# 05_Data.net
KiCad netlist of a schematic drawn in Altium Designer
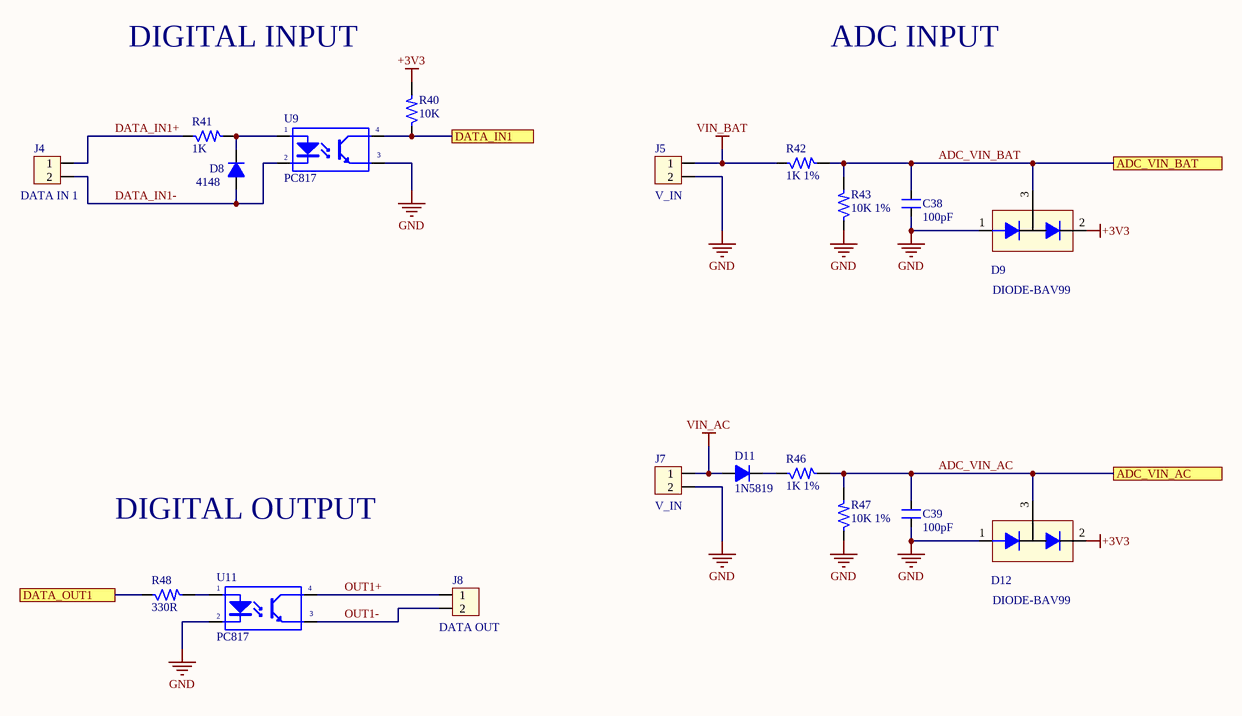
[diagram p0: [05] Data.SchDoc]

(export (version "E")
  (design (tool "Eeschema 10.0.6"))
  (components
    (comp (ref "C38")
      (value "100pF")
      (footprint "C0603 SMT")
      (description "Cap SMD")
      (libsource (lib "khapham") (part "CM"))
    )
    (comp (ref "C39")
      (value "100pF")
      (footprint "C0603 SMT")
      (description "Cap SMD")
      (libsource (lib "khapham") (part "CM"))
    )
    (comp (ref "D8")
      (value "4148")
      (footprint "DO-4148 SMD")
      (description "Diode 1A")
      (libsource (lib "khapham") (part "D1A"))
    )
    (comp (ref "D9")
      (value "DIODE-BAV99")
      (footprint "SOT23")
      (description "ZENER, SOT23,")
      (fields
        (field (name "MANUFACTURER") "ON Semiconductor / Fairchild")
        (field (name "MANUFACTURER PART NUMBER") "BAV99")
        (field (name ".CREATOR") "LeKhaLinh")
        (field (name ".CHECKPCB") "LeKhaLinh")
        (field (name ".CHECKSCH") "LeKhaLinh")
      )
      (libsource (lib "khapham") (part "DIODE-BAV99"))
    )
    (comp (ref "D11")
      (value "1N5819")
      (footprint "SOD123")
      (description "Diode 1A")
      (libsource (lib "khapham") (part "D1A"))
    )
    (comp (ref "D12")
      (value "DIODE-BAV99")
      (footprint "SOT23")
      (description "ZENER, SOT23,")
      (fields
        (field (name "MANUFACTURER") "ON Semiconductor / Fairchild")
        (field (name "MANUFACTURER PART NUMBER") "BAV99")
        (field (name ".CREATOR") "LeKhaLinh")
        (field (name ".CHECKPCB") "LeKhaLinh")
        (field (name ".CHECKSCH") "LeKhaLinh")
      )
      (libsource (lib "khapham") (part "DIODE-BAV99"))
    )
    (comp (ref "J4")
      (value "DATA IN 1")
      (footprint "CON_2.54mm_2")
      (description "Connector 2")
      (libsource (lib "khapham") (part "Con2"))
    )
    (comp (ref "J5")
      (value "V_IN")
      (footprint "CON_2.54mm_2")
      (description "Connector 2")
      (libsource (lib "khapham") (part "Con2"))
    )
    (comp (ref "J7")
      (value "V_IN")
      (footprint "CON_2.54mm_2")
      (description "Connector 2")
      (libsource (lib "khapham") (part "Con2"))
    )
    (comp (ref "J8")
      (value "DATA OUT")
      (footprint "CON_2.54mm_2")
      (description "Connector 2")
      (libsource (lib "") (part "Con2_1"))
    )
    (comp (ref "R40")
      (value "10K")
      (footprint "R0603 -SMT")
      (description "Resistor SMD")
      (libsource (lib "khapham") (part "RM"))
    )
    (comp (ref "R41")
      (value "1K")
      (footprint "R0603 -SMT")
      (description "Resistor SMD")
      (libsource (lib "khapham") (part "RM"))
    )
    (comp (ref "R42")
      (value "1K 1%")
      (footprint "R0603 -SMT")
      (description "Resistor SMD")
      (libsource (lib "khapham") (part "RM"))
    )
    (comp (ref "R43")
      (value "10K 1%")
      (footprint "R0603 -SMT")
      (description "Resistor SMD")
      (libsource (lib "khapham") (part "RM"))
    )
    (comp (ref "R46")
      (value "1K 1%")
      (footprint "R0603 -SMT")
      (description "Resistor SMD")
      (libsource (lib "khapham") (part "RM"))
    )
    (comp (ref "R47")
      (value "10K 1%")
      (footprint "R0603 -SMT")
      (description "Resistor SMD")
      (libsource (lib "khapham") (part "RM"))
    )
    (comp (ref "R48")
      (value "330R")
      (footprint "R0603 -SMT")
      (description "Resistor SMD")
      (libsource (lib "khapham") (part "RM"))
    )
    (comp (ref "U9")
      (value "PC817")
      (footprint "SOP-4-B")
      (description "Single Opto")
      (libsource (lib "khapham") (part "PC817"))
    )
    (comp (ref "U11")
      (value "PC817")
      (footprint "SOP-4-B")
      (description "Single Opto")
      (libsource (lib "khapham") (part "PC817"))
    )
  )
  (nets
    (net (code "1") (name "+3V3") (class "Default")
      (node (ref "D12") (pin "2") (pinfunction "2_2") (pintype "passive"))
      (node (ref "D9") (pin "2") (pinfunction "2_2") (pintype "passive"))
      (node (ref "R40") (pin "2") (pinfunction "2_2") (pintype "passive"))
    )
    (net (code "2") (name "/ADC_VIN_AC") (class "Default")
      (node (ref "C39") (pin "2") (pinfunction "2_2") (pintype "passive"))
      (node (ref "D12") (pin "3") (pinfunction "3_3") (pintype "passive"))
      (node (ref "R46") (pin "2") (pinfunction "2_2") (pintype "passive"))
      (node (ref "R47") (pin "2") (pinfunction "2_2") (pintype "passive"))
    )
    (net (code "3") (name "/ADC_VIN_BAT") (class "Default")
      (node (ref "C38") (pin "2") (pinfunction "2_2") (pintype "passive"))
      (node (ref "D9") (pin "3") (pinfunction "3_3") (pintype "passive"))
      (node (ref "R42") (pin "2") (pinfunction "2_2") (pintype "passive"))
      (node (ref "R43") (pin "2") (pinfunction "2_2") (pintype "passive"))
    )
    (net (code "4") (name "/DATA_IN1") (class "Default")
      (node (ref "R40") (pin "1") (pinfunction "1_1") (pintype "passive"))
      (node (ref "U9") (pin "4") (pinfunction "C_4") (pintype "passive"))
    )
    (net (code "5") (name "/DATA_IN1+") (class "Default")
      (node (ref "J4") (pin "1") (pinfunction "1_1") (pintype "passive"))
      (node (ref "R41") (pin "1") (pinfunction "1_1") (pintype "passive"))
    )
    (net (code "6") (name "/DATA_IN1-") (class "Default")
      (node (ref "D8") (pin "1") (pinfunction "A_1") (pintype "passive"))
      (node (ref "J4") (pin "2") (pinfunction "2_2") (pintype "passive"))
      (node (ref "U9") (pin "2") (pinfunction "K_2") (pintype "passive"))
    )
    (net (code "7") (name "/DATA_OUT1") (class "Default")
      (node (ref "R48") (pin "1") (pinfunction "1_1") (pintype "passive"))
    )
    (net (code "8") (name "/OUT1+") (class "Default")
      (node (ref "J8") (pin "1") (pinfunction "1_1") (pintype "passive"))
      (node (ref "U11") (pin "4") (pinfunction "C_4") (pintype "passive"))
    )
    (net (code "9") (name "/OUT1-") (class "Default")
      (node (ref "J8") (pin "2") (pinfunction "2_2") (pintype "passive"))
      (node (ref "U11") (pin "3") (pinfunction "E_3") (pintype "passive"))
    )
    (net (code "10") (name "GND") (class "Default")
      (node (ref "C38") (pin "1") (pinfunction "1_1") (pintype "passive"))
      (node (ref "C39") (pin "1") (pinfunction "1_1") (pintype "passive"))
      (node (ref "D12") (pin "1") (pinfunction "1_1") (pintype "passive"))
      (node (ref "D9") (pin "1") (pinfunction "1_1") (pintype "passive"))
      (node (ref "J5") (pin "2") (pinfunction "2_2") (pintype "passive"))
      (node (ref "J7") (pin "2") (pinfunction "2_2") (pintype "passive"))
      (node (ref "R43") (pin "1") (pinfunction "1_1") (pintype "passive"))
      (node (ref "R47") (pin "1") (pinfunction "1_1") (pintype "passive"))
      (node (ref "U11") (pin "2") (pinfunction "K_2") (pintype "passive"))
      (node (ref "U9") (pin "3") (pinfunction "E_3") (pintype "passive"))
    )
    (net (code "11") (name "Net-(D8-K)") (class "Default")
      (node (ref "D8") (pin "2") (pinfunction "K_2") (pintype "passive"))
      (node (ref "R41") (pin "2") (pinfunction "2_2") (pintype "passive"))
      (node (ref "U9") (pin "1") (pinfunction "A_1") (pintype "passive"))
    )
    (net (code "12") (name "Net-(D11-K)") (class "Default")
      (node (ref "D11") (pin "2") (pinfunction "K_2") (pintype "passive"))
      (node (ref "R46") (pin "1") (pinfunction "1_1") (pintype "passive"))
    )
    (net (code "13") (name "Net-(U11-A)") (class "Default")
      (node (ref "R48") (pin "2") (pinfunction "2_2") (pintype "passive"))
      (node (ref "U11") (pin "1") (pinfunction "A_1") (pintype "passive"))
    )
    (net (code "14") (name "VIN_AC") (class "Default")
      (node (ref "D11") (pin "1") (pinfunction "A_1") (pintype "passive"))
      (node (ref "J7") (pin "1") (pinfunction "1_1") (pintype "passive"))
    )
    (net (code "15") (name "VIN_BAT") (class "Default")
      (node (ref "J5") (pin "1") (pinfunction "1_1") (pintype "passive"))
      (node (ref "R42") (pin "1") (pinfunction "1_1") (pintype "passive"))
    )
  )
)
